# NodeLight.net
KiCad netlist of a schematic drawn in EAGLE
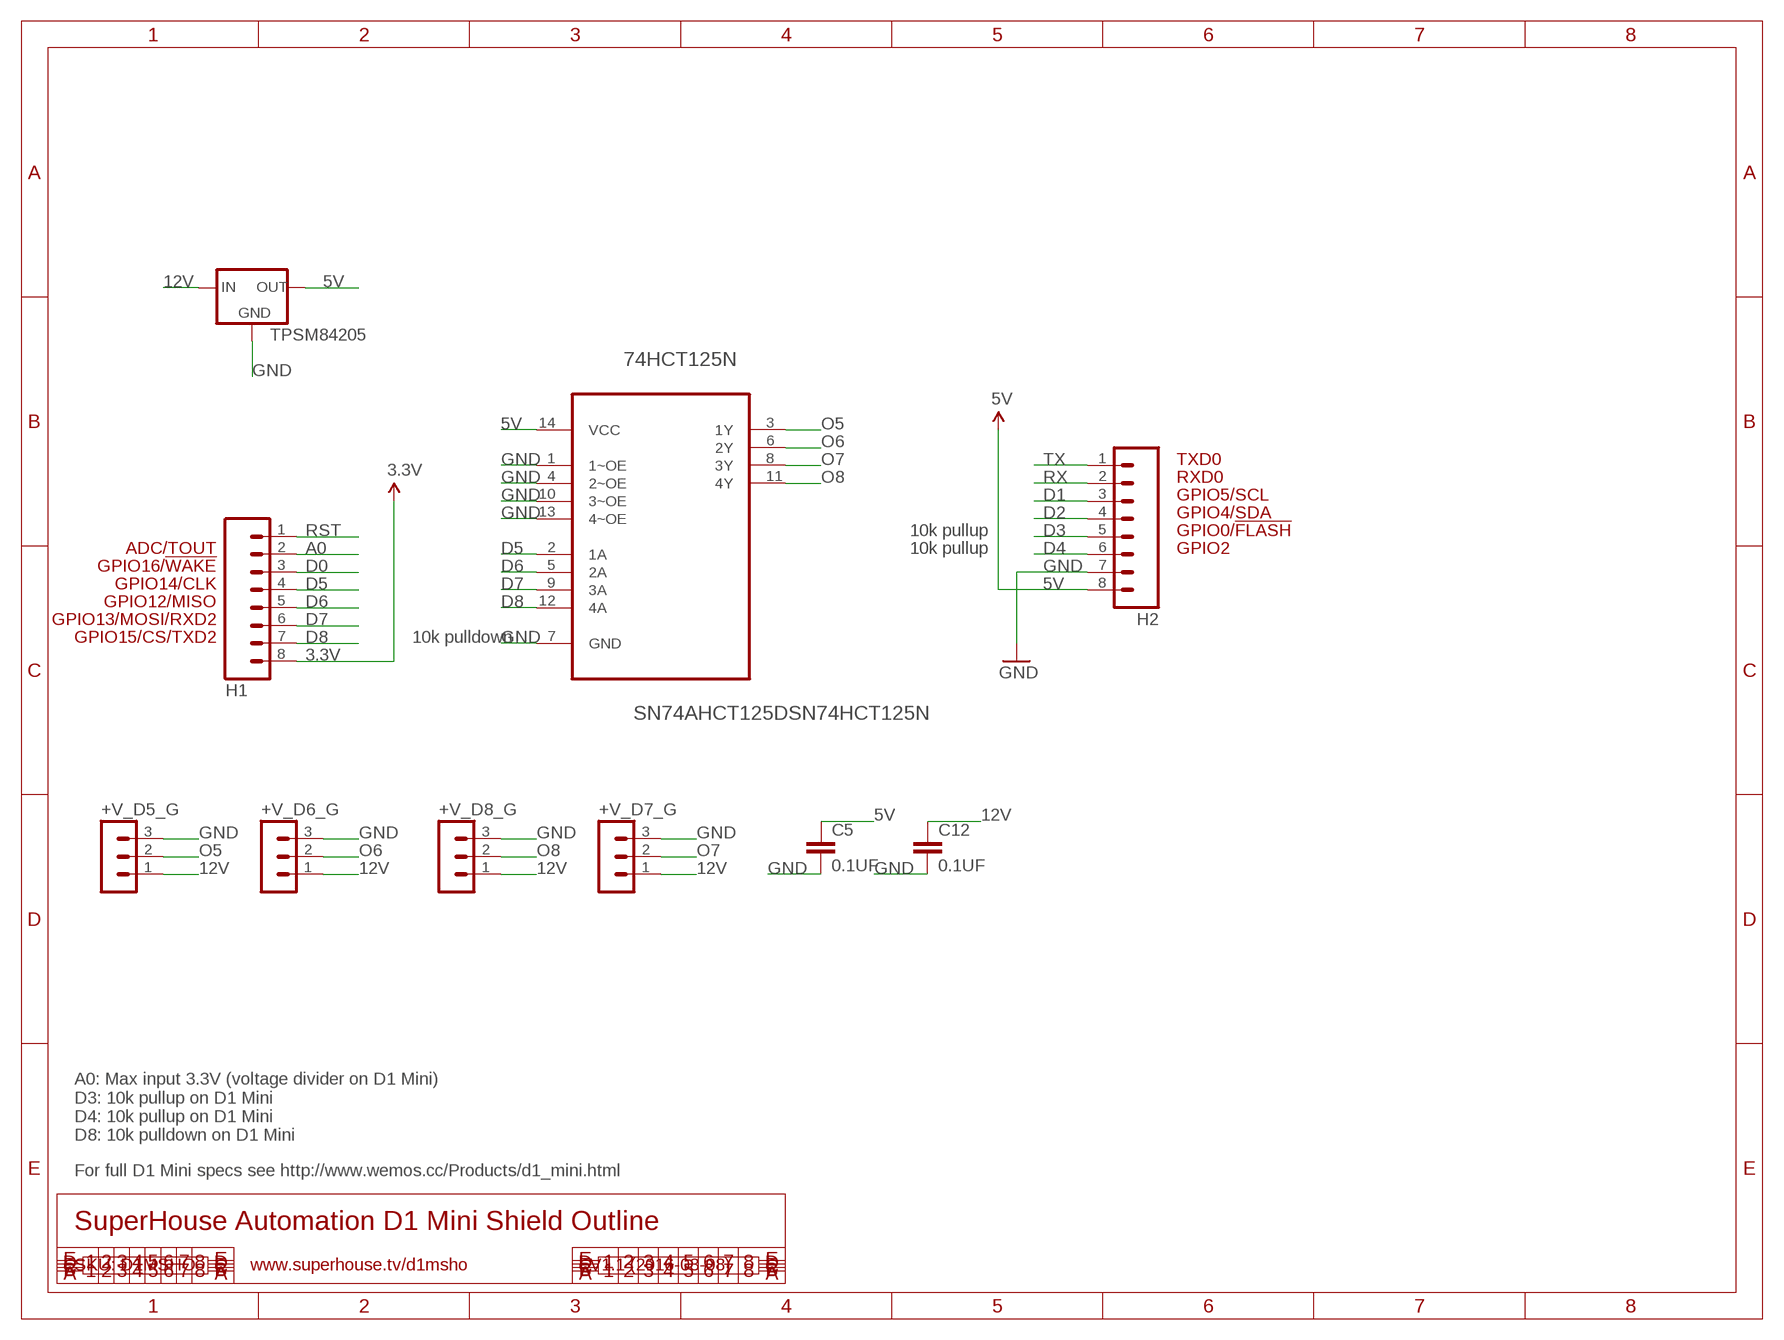
[diagram p0: schematic, sheet 1]

(export (version "E")
  (design (tool "Eeschema 10.0.6"))
  (components
    (comp (ref "+V_D5_G")
      (value "MA03-1")
      (footprint "eagle-import:MA03-1")
      (libsource (lib "eagle-import") (part "MA03-1"))
    )
    (comp (ref "+V_D6_G")
      (value "MA03-1")
      (footprint "eagle-import:MA03-1")
      (libsource (lib "eagle-import") (part "MA03-1"))
    )
    (comp (ref "+V_D7_G")
      (value "MA03-1")
      (footprint "eagle-import:MA03-1")
      (libsource (lib "eagle-import") (part "MA03-1"))
    )
    (comp (ref "+V_D8_G")
      (value "MA03-1")
      (footprint "eagle-import:MA03-1")
      (libsource (lib "eagle-import") (part "MA03-1"))
    )
    (comp (ref "74HCT125N")
      (value "SN74AHCT125DSN74HCT125N")
      (footprint "eagle-import:DIP254P762X508-14")
      (libsource (lib "eagle-import") (part "SN74AHCT125DSN74HCT125N"))
    )
    (comp (ref "C5")
      (value "0.1UF")
      (footprint "eagle-import:C025-025X050")
      (libsource (lib "eagle-import") (part "C-EU025-025X050"))
    )
    (comp (ref "C12")
      (value "0.1UF")
      (footprint "eagle-import:C025-025X050")
      (libsource (lib "eagle-import") (part "C-EU025-025X050"))
    )
    (comp (ref "H1")
      (value "M08")
      (footprint "eagle-import:1X08")
      (libsource (lib "eagle-import") (part "M08"))
    )
    (comp (ref "H2")
      (value "M08")
      (footprint "eagle-import:1X08")
      (libsource (lib "eagle-import") (part "M08"))
    )
    (comp (ref "TPSM84205")
      (value "78MXXS")
      (footprint "eagle-import:78MXXS")
      (libsource (lib "eagle-import") (part "78MXXS"))
    )
  )
  (nets
    (net (code "1") (name "/12V") (class "Default")
      (node (ref "+V_D5_G") (pin "1") (pinfunction "1_1") (pintype "passive"))
      (node (ref "+V_D6_G") (pin "1") (pinfunction "1_1") (pintype "passive"))
      (node (ref "+V_D7_G") (pin "1") (pinfunction "1_1") (pintype "passive"))
      (node (ref "+V_D8_G") (pin "1") (pinfunction "1_1") (pintype "passive"))
      (node (ref "C12") (pin "1") (pinfunction "1_1") (pintype "passive"))
      (node (ref "TPSM84205") (pin "IN") (pinfunction "IN_IN") (pintype "input"))
    )
    (net (code "2") (name "/A0") (class "Default")
      (node (ref "H1") (pin "2") (pinfunction "2_2") (pintype "passive"))
    )
    (net (code "3") (name "/D0") (class "Default")
      (node (ref "H1") (pin "3") (pinfunction "3_3") (pintype "passive"))
    )
    (net (code "4") (name "/D1") (class "Default")
      (node (ref "H2") (pin "3") (pinfunction "3_3") (pintype "passive"))
    )
    (net (code "5") (name "/D2") (class "Default")
      (node (ref "H2") (pin "4") (pinfunction "4_4") (pintype "passive"))
    )
    (net (code "6") (name "/D3") (class "Default")
      (node (ref "H2") (pin "5") (pinfunction "5_5") (pintype "passive"))
    )
    (net (code "7") (name "/D4") (class "Default")
      (node (ref "H2") (pin "6") (pinfunction "6_6") (pintype "passive"))
    )
    (net (code "8") (name "/D5") (class "Default")
      (node (ref "74HCT125N") (pin "2") (pinfunction "1A_2") (pintype "input"))
      (node (ref "H1") (pin "4") (pinfunction "4_4") (pintype "passive"))
    )
    (net (code "9") (name "/D6") (class "Default")
      (node (ref "74HCT125N") (pin "5") (pinfunction "2A_5") (pintype "input"))
      (node (ref "H1") (pin "5") (pinfunction "5_5") (pintype "passive"))
    )
    (net (code "10") (name "/D7") (class "Default")
      (node (ref "74HCT125N") (pin "9") (pinfunction "3A_9") (pintype "input"))
      (node (ref "H1") (pin "6") (pinfunction "6_6") (pintype "passive"))
    )
    (net (code "11") (name "/D8") (class "Default")
      (node (ref "74HCT125N") (pin "12") (pinfunction "4A_12") (pintype "input"))
      (node (ref "H1") (pin "7") (pinfunction "7_7") (pintype "passive"))
    )
    (net (code "12") (name "/O5") (class "Default")
      (node (ref "+V_D5_G") (pin "2") (pinfunction "2_2") (pintype "passive"))
      (node (ref "74HCT125N") (pin "3") (pinfunction "1Y_3") (pintype "output"))
    )
    (net (code "13") (name "/O6") (class "Default")
      (node (ref "+V_D6_G") (pin "2") (pinfunction "2_2") (pintype "passive"))
      (node (ref "74HCT125N") (pin "6") (pinfunction "2Y_6") (pintype "output"))
    )
    (net (code "14") (name "/O7") (class "Default")
      (node (ref "+V_D7_G") (pin "2") (pinfunction "2_2") (pintype "passive"))
      (node (ref "74HCT125N") (pin "8") (pinfunction "3Y_8") (pintype "output"))
    )
    (net (code "15") (name "/O8") (class "Default")
      (node (ref "+V_D8_G") (pin "2") (pinfunction "2_2") (pintype "passive"))
      (node (ref "74HCT125N") (pin "11") (pinfunction "4Y_11") (pintype "output"))
    )
    (net (code "16") (name "/RST") (class "Default")
      (node (ref "H1") (pin "1") (pinfunction "1_1") (pintype "passive"))
    )
    (net (code "17") (name "/RX") (class "Default")
      (node (ref "H2") (pin "2") (pinfunction "2_2") (pintype "passive"))
    )
    (net (code "18") (name "/TX") (class "Default")
      (node (ref "H2") (pin "1") (pinfunction "1_1") (pintype "passive"))
    )
    (net (code "19") (name "3.3V") (class "Default")
      (node (ref "H1") (pin "8") (pinfunction "8_8") (pintype "passive"))
    )
    (net (code "20") (name "5V") (class "Default")
      (node (ref "74HCT125N") (pin "14") (pinfunction "VCC_14") (pintype "power_in"))
      (node (ref "C5") (pin "1") (pinfunction "1_1") (pintype "passive"))
      (node (ref "H2") (pin "8") (pinfunction "8_8") (pintype "passive"))
      (node (ref "TPSM84205") (pin "OUT") (pinfunction "OUT_OUT") (pintype "passive"))
    )
    (net (code "21") (name "GND") (class "Default")
      (node (ref "+V_D5_G") (pin "3") (pinfunction "3_3") (pintype "passive"))
      (node (ref "+V_D6_G") (pin "3") (pinfunction "3_3") (pintype "passive"))
      (node (ref "+V_D7_G") (pin "3") (pinfunction "3_3") (pintype "passive"))
      (node (ref "+V_D8_G") (pin "3") (pinfunction "3_3") (pintype "passive"))
      (node (ref "74HCT125N") (pin "1") (pinfunction "1~{OE}_1") (pintype "input"))
      (node (ref "74HCT125N") (pin "10") (pinfunction "3~{OE}_10") (pintype "input"))
      (node (ref "74HCT125N") (pin "13") (pinfunction "4~{OE}_13") (pintype "input"))
      (node (ref "74HCT125N") (pin "4") (pinfunction "2~{OE}_4") (pintype "input"))
      (node (ref "74HCT125N") (pin "7") (pinfunction "GND_7") (pintype "passive"))
      (node (ref "C12") (pin "2") (pinfunction "2_2") (pintype "passive"))
      (node (ref "C5") (pin "2") (pinfunction "2_2") (pintype "passive"))
      (node (ref "H2") (pin "7") (pinfunction "7_7") (pintype "passive"))
      (node (ref "TPSM84205") (pin "GND") (pinfunction "GND_GND") (pintype "input"))
    )
  )
)
